# wk2.net
KiCad netlist of a schematic drawn in EAGLE
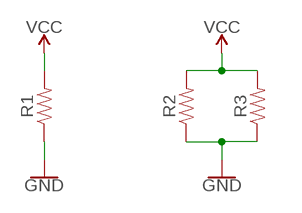
[diagram p0: schematic, sheet 1]

(export (version "E")
  (design (tool "Eeschema 10.0.6"))
  (components
    (comp (ref "R1")
      (value "RESISTORAXIAL-0.3")
      (footprint "eagle-import:AXIAL-0.3")
      (libsource (lib "eagle-import") (part "RESISTORAXIAL-0.3"))
    )
    (comp (ref "R2")
      (value "RESISTORAXIAL-0.3")
      (footprint "eagle-import:AXIAL-0.3")
      (libsource (lib "eagle-import") (part "RESISTORAXIAL-0.3"))
    )
    (comp (ref "R3")
      (value "RESISTORAXIAL-0.3")
      (footprint "eagle-import:AXIAL-0.3")
      (libsource (lib "eagle-import") (part "RESISTORAXIAL-0.3"))
    )
  )
  (nets
    (net (code "1") (name "GND") (class "Default")
      (node (ref "R1") (pin "P$1") (pinfunction "1_P$1") (pintype "passive"))
      (node (ref "R2") (pin "P$1") (pinfunction "1_P$1") (pintype "passive"))
      (node (ref "R3") (pin "P$1") (pinfunction "1_P$1") (pintype "passive"))
    )
    (net (code "2") (name "VCC") (class "Default")
      (node (ref "R1") (pin "P$2") (pinfunction "2_P$2") (pintype "passive"))
      (node (ref "R2") (pin "P$2") (pinfunction "2_P$2") (pintype "passive"))
      (node (ref "R3") (pin "P$2") (pinfunction "2_P$2") (pintype "passive"))
    )
  )
)
